# SENSORS.net
KiCad netlist of a schematic drawn in Altium Designer
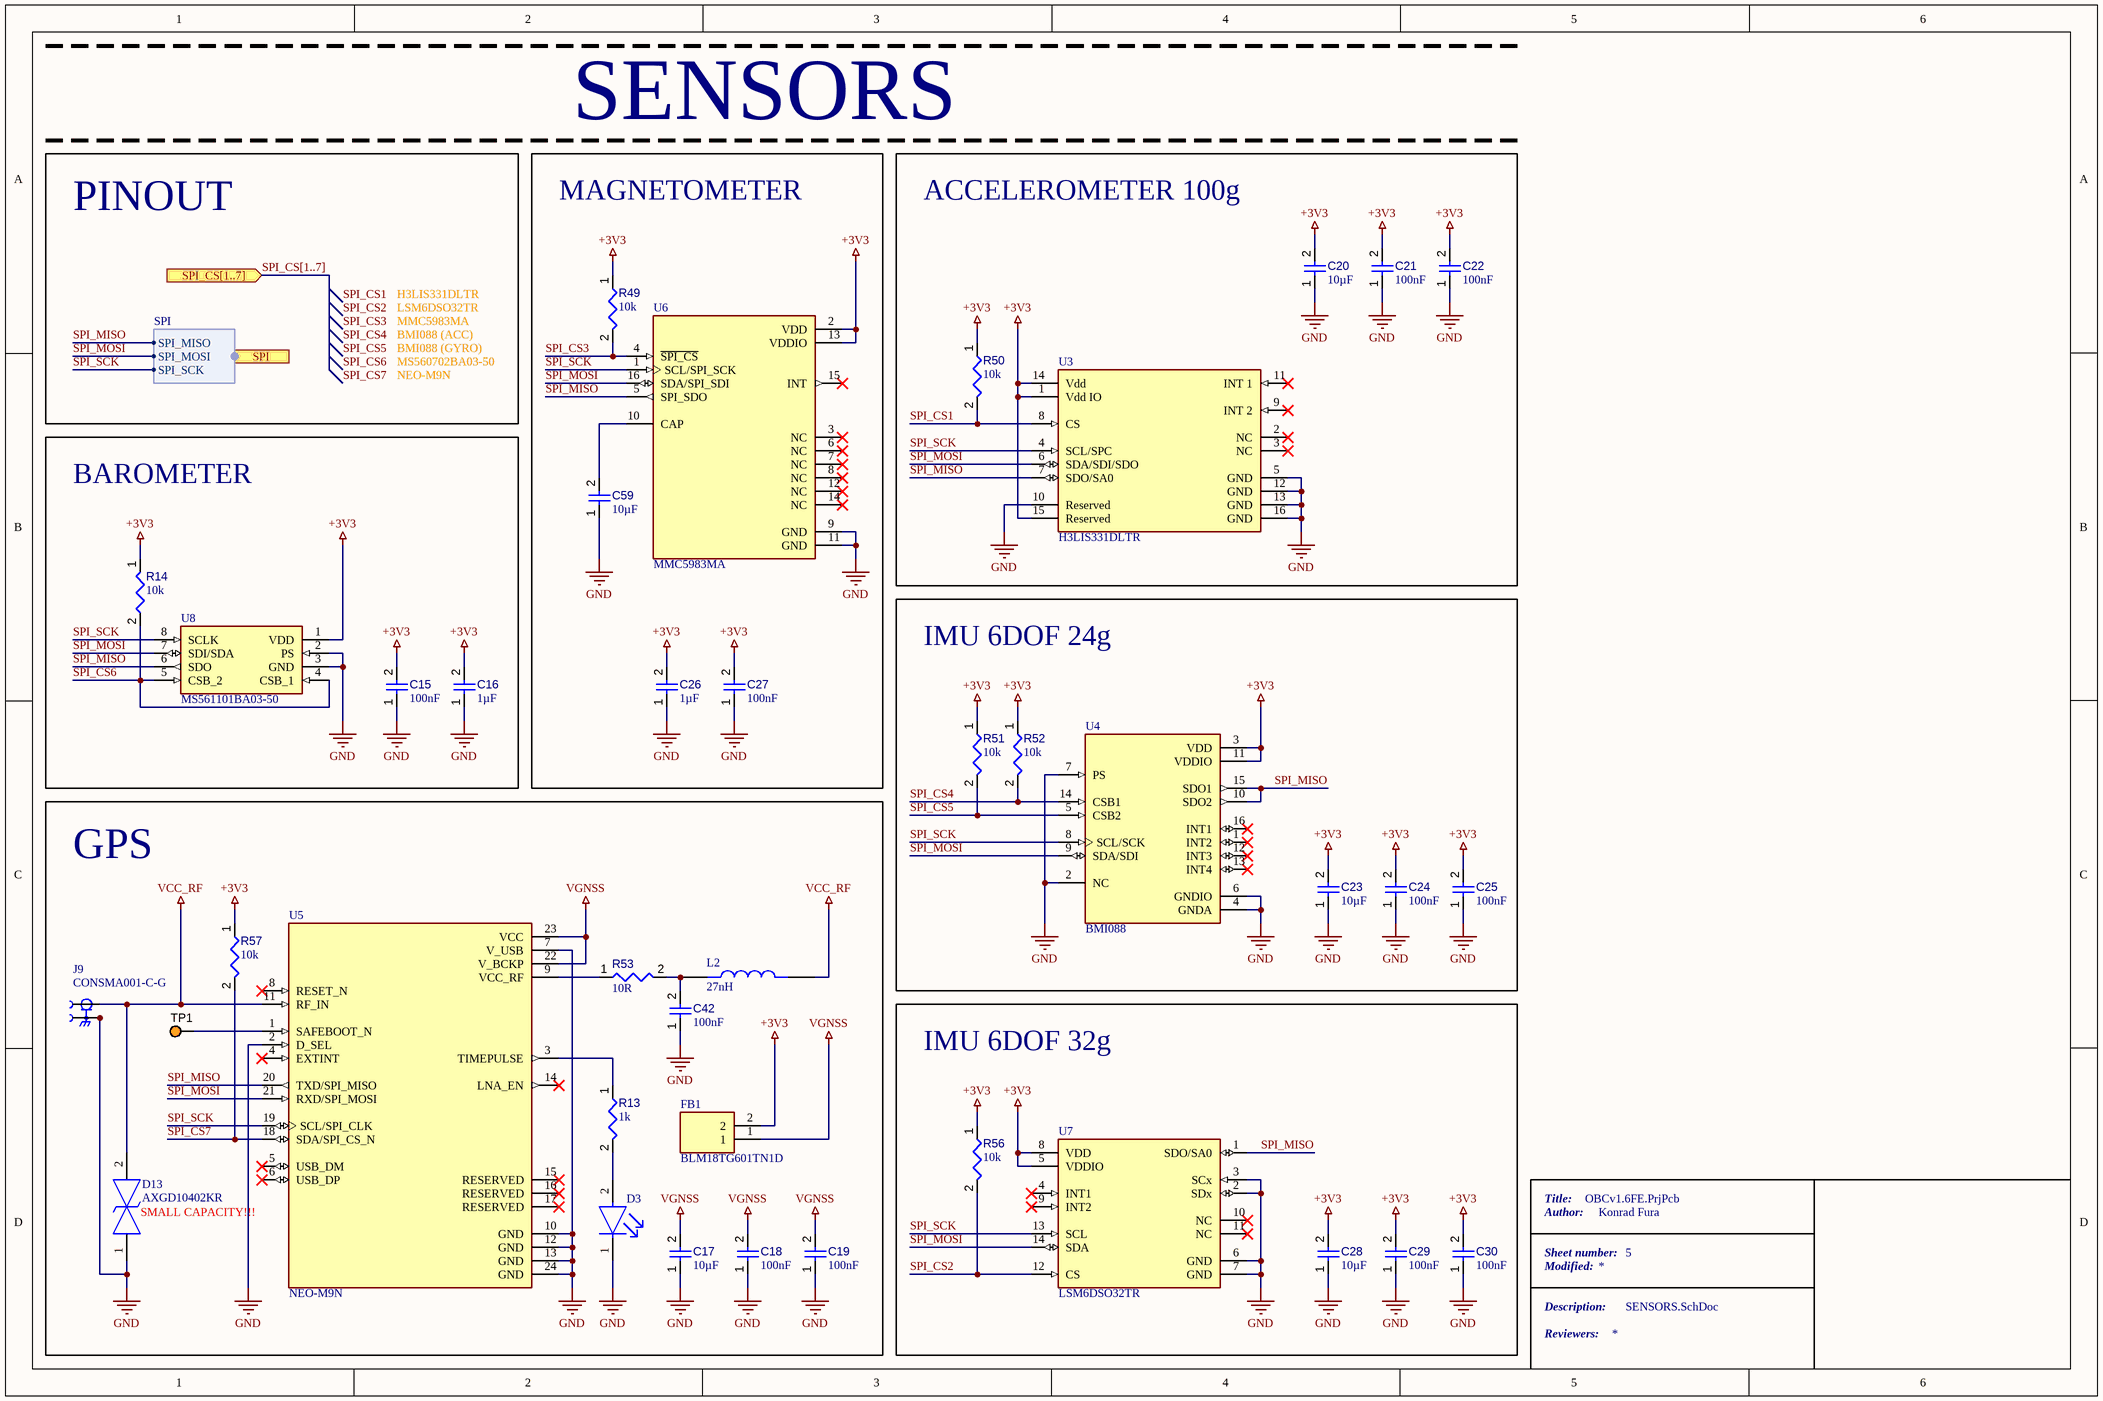
[diagram p0: SENSORS.SchDoc]

(export (version "E")
  (design (tool "Eeschema 10.0.6"))
  (components
    (comp (ref "C15")
      (value "100nF")
      (footprint "CAPC0402(1005)60_L")
      (description "Chip Capacitor, 100nF +/-20%, 10V, 0402, Thickness 0.6 mm")
      (fields (field (name "TOLERANCE") "20%") (field (name "Comment") "Capacitor 100nF +/-20% 10V 0402"))
      (libsource (lib "PWr in Space team") (part "CAP-NP-2"))
    )
    (comp (ref "C16")
      (value "1µF")
      (footprint "CAPC0402(1005)60_L")
      (description "Chip Capacitor, 1µF +/-20%, 10V, 0402, Thickness 0.6 mm")
      (fields (field (name "TOLERANCE") "10%") (field (name "Comment") "Capacitor 1µF +/-20% 10V 0402"))
      (libsource (lib "PWr in Space team") (part "CAP-NP-2"))
    )
    (comp (ref "C17")
      (value "10µF")
      (footprint "CAPC0603(1608)100_L")
      (description "Chip Capacitor, 10µF +/-20%, 10V, 0603, Thickness 1 mm")
      (fields (field (name "TOLERANCE") "10%") (field (name "Comment") "Capacitor 10µF +/-20% 10V 0603"))
      (libsource (lib "PWr in Space team") (part "CAP-NP-2"))
    )
    (comp (ref "C18")
      (value "100nF")
      (footprint "CAPC0402(1005)60_L")
      (description "Chip Capacitor, 100nF +/-20%, 10V, 0402, Thickness 0.6 mm")
      (fields (field (name "TOLERANCE") "20%") (field (name "Comment") "Capacitor 100nF +/-20% 10V 0402"))
      (libsource (lib "PWr in Space team") (part "CAP-NP-2"))
    )
    (comp (ref "C19")
      (value "100nF")
      (footprint "CAPC0402(1005)60_L")
      (description "Chip Capacitor, 100nF +/-20%, 10V, 0402, Thickness 0.6 mm")
      (fields (field (name "TOLERANCE") "20%") (field (name "Comment") "Capacitor 100nF +/-20% 10V 0402"))
      (libsource (lib "PWr in Space team") (part "CAP-NP-2"))
    )
    (comp (ref "C20")
      (value "10µF")
      (footprint "CAPC0603(1608)100_L")
      (description "Chip Capacitor, 10µF +/-20%, 10V, 0603, Thickness 1 mm")
      (fields (field (name "TOLERANCE") "10%") (field (name "Comment") "Capacitor 10µF +/-20% 10V 0603"))
      (libsource (lib "PWr in Space team") (part "CAP-NP-2"))
    )
    (comp (ref "C21")
      (value "100nF")
      (footprint "CAPC0402(1005)60_L")
      (description "Chip Capacitor, 100nF +/-20%, 10V, 0402, Thickness 0.6 mm")
      (fields (field (name "TOLERANCE") "20%") (field (name "Comment") "Capacitor 100nF +/-20% 10V 0402"))
      (libsource (lib "PWr in Space team") (part "CAP-NP-2"))
    )
    (comp (ref "C22")
      (value "100nF")
      (footprint "CAPC0402(1005)60_L")
      (description "Chip Capacitor, 100nF +/-20%, 10V, 0402, Thickness 0.6 mm")
      (fields (field (name "TOLERANCE") "20%") (field (name "Comment") "Capacitor 100nF +/-20% 10V 0402"))
      (libsource (lib "PWr in Space team") (part "CAP-NP-2"))
    )
    (comp (ref "C23")
      (value "10µF")
      (footprint "CAPC0603(1608)100_L")
      (description "Chip Capacitor, 10µF +/-20%, 10V, 0603, Thickness 1 mm")
      (fields (field (name "TOLERANCE") "10%") (field (name "Comment") "Capacitor 10µF +/-20% 10V 0603"))
      (libsource (lib "PWr in Space team") (part "CAP-NP-2"))
    )
    (comp (ref "C24")
      (value "100nF")
      (footprint "CAPC0402(1005)60_L")
      (description "Chip Capacitor, 100nF +/-20%, 10V, 0402, Thickness 0.6 mm")
      (fields (field (name "TOLERANCE") "20%") (field (name "Comment") "Capacitor 100nF +/-20% 10V 0402"))
      (libsource (lib "PWr in Space team") (part "CAP-NP-2"))
    )
    (comp (ref "C25")
      (value "100nF")
      (footprint "CAPC0402(1005)60_L")
      (description "Chip Capacitor, 100nF +/-20%, 10V, 0402, Thickness 0.6 mm")
      (fields (field (name "TOLERANCE") "20%") (field (name "Comment") "Capacitor 100nF +/-20% 10V 0402"))
      (libsource (lib "PWr in Space team") (part "CAP-NP-2"))
    )
    (comp (ref "C26")
      (value "1µF")
      (footprint "CAPC0402(1005)60_L")
      (description "Chip Capacitor, 1µF +/-20%, 10V, 0402, Thickness 0.6 mm")
      (fields (field (name "TOLERANCE") "10%") (field (name "Comment") "Capacitor 1µF +/-20% 10V 0402"))
      (libsource (lib "PWr in Space team") (part "CAP-NP-2"))
    )
    (comp (ref "C27")
      (value "100nF")
      (footprint "CAPC0402(1005)60_L")
      (description "Chip Capacitor, 100nF +/-20%, 10V, 0402, Thickness 0.6 mm")
      (fields (field (name "TOLERANCE") "20%") (field (name "Comment") "Capacitor 100nF +/-20% 10V 0402"))
      (libsource (lib "PWr in Space team") (part "CAP-NP-2"))
    )
    (comp (ref "C28")
      (value "10µF")
      (footprint "CAPC0603(1608)100_L")
      (description "Chip Capacitor, 10µF +/-20%, 10V, 0603, Thickness 1 mm")
      (fields (field (name "TOLERANCE") "10%") (field (name "Comment") "Capacitor 10µF +/-20% 10V 0603"))
      (libsource (lib "PWr in Space team") (part "CAP-NP-2"))
    )
    (comp (ref "C29")
      (value "100nF")
      (footprint "CAPC0402(1005)60_L")
      (description "Chip Capacitor, 100nF +/-20%, 10V, 0402, Thickness 0.6 mm")
      (fields (field (name "TOLERANCE") "20%") (field (name "Comment") "Capacitor 100nF +/-20% 10V 0402"))
      (libsource (lib "PWr in Space team") (part "CAP-NP-2"))
    )
    (comp (ref "C30")
      (value "100nF")
      (footprint "CAPC0402(1005)60_L")
      (description "Chip Capacitor, 100nF +/-20%, 10V, 0402, Thickness 0.6 mm")
      (fields (field (name "TOLERANCE") "20%") (field (name "Comment") "Capacitor 100nF +/-20% 10V 0402"))
      (libsource (lib "PWr in Space team") (part "CAP-NP-2"))
    )
    (comp (ref "C42")
      (value "100nF")
      (footprint "CAPC0402(1005)60_L")
      (description "Chip Capacitor, 100nF +/-20%, 10V, 0402, Thickness 0.6 mm")
      (fields (field (name "TOLERANCE") "20%") (field (name "Comment") "Capacitor 100nF +/-20% 10V 0402"))
      (libsource (lib "PWr in Space team") (part "CAP-NP-2"))
    )
    (comp (ref "C59")
      (value "10µF")
      (footprint "CAPC0603(1608)100_L")
      (description "Chip Capacitor, 10µF +/-20%, 10V, 0603, Thickness 1 mm")
      (fields (field (name "TOLERANCE") "10%") (field (name "Comment") "Capacitor 10µF +/-20% 10V 0603"))
      (libsource (lib "PWr in Space team") (part "CAP-NP-2"))
    )
    (comp (ref "D3")
      (value "D3")
      (footprint "FP-LTST-C191TBKT-MFG")
      (description "LED BLUE CLEAR CHIP SMD")
      (libsource (lib "Altium Content Vault") (part "8706943c75ba83719d021d2fdc84c58"))
    )
    (comp (ref "D13")
      (value "AXGD10402KR")
      (footprint "SamacSys:DIONM105X51N")
      (description "TVS Diode (Bi-directional)")
      (fields (field (name "MOUSER PART NUMBER") "576-AXGD10402KR"))
      (libsource (lib "*") (part "AXGD10402KR"))
    )
    (comp (ref "FB1")
      (value "BLM18TG601TN1D")
      (footprint "SamacSys:BLM18EG101TH1D")
      (description "Ferrite Bead")
      (fields (field (name "MOUSER PART NUMBER") "81-BLM18TG601TN1D"))
      (libsource (lib "*") (part "BLM18TG601TN1D"))
    )
    (comp (ref "J9")
      (value "CONSMA001-C-G")
      (footprint "LINX_CONSMA001-C-G")
      (fields (field (name "MF") "{'manufacturer': u'Linx Technologies'}"))
      (libsource (lib "SnapEDA_Library") (part "CONSMA001-C-G"))
    )
    (comp (ref "L2")
      (value "27nH")
      (footprint "INDC1005X65N")
      (description "IND 27nH 0.3A 1000mâ„¦")
      (fields (field (name "MF") "{'manufacturer': u'Abracon'}") (field (name "MP") "AIMC-0402-27NJ-T"))
      (libsource (lib "SnapEDA_Library") (part "AIMC-0402-27NJ-T"))
    )
    (comp (ref "R13")
      (value "1k")
      (footprint "RESC0402(1005)_L")
      (description "Chip Resistor, 1 kOhms, +/-5 %, 63 mW, -55 to 155 degC, 0402")
      (fields (field (name "TOLERANCE") "5%") (field (name "POWER") "63mW"))
      (libsource (lib "PWr in Space team") (part "RES-2"))
    )
    (comp (ref "R14")
      (value "10k")
      (footprint "RESC0402(1005)_L")
      (description "Chip Resistor, 10 kOhms, +/-1 %, 63 mW, -55 to 125 degC, 0402")
      (fields (field (name "POWER") "63mW") (field (name "TOLERANCE") "1%"))
      (libsource (lib "PWr in Space team") (part "RES-2"))
    )
    (comp (ref "R49")
      (value "10k")
      (footprint "RESC0402(1005)_L")
      (description "Chip Resistor, 10 kOhms, +/-1 %, 63 mW, -55 to 125 degC, 0402")
      (fields (field (name "POWER") "63mW") (field (name "TOLERANCE") "1%"))
      (libsource (lib "PWr in Space team") (part "RES-2"))
    )
    (comp (ref "R50")
      (value "10k")
      (footprint "RESC0402(1005)_L")
      (description "Chip Resistor, 10 kOhms, +/-1 %, 63 mW, -55 to 125 degC, 0402")
      (fields (field (name "POWER") "63mW") (field (name "TOLERANCE") "1%"))
      (libsource (lib "PWr in Space team") (part "RES-2"))
    )
    (comp (ref "R51")
      (value "10k")
      (footprint "RESC0402(1005)_L")
      (description "Chip Resistor, 10 kOhms, +/-1 %, 63 mW, -55 to 125 degC, 0402")
      (fields (field (name "POWER") "63mW") (field (name "TOLERANCE") "1%"))
      (libsource (lib "PWr in Space team") (part "RES-2"))
    )
    (comp (ref "R52")
      (value "10k")
      (footprint "RESC0402(1005)_L")
      (description "Chip Resistor, 10 kOhms, +/-1 %, 63 mW, -55 to 125 degC, 0402")
      (fields (field (name "POWER") "63mW") (field (name "TOLERANCE") "1%"))
      (libsource (lib "PWr in Space team") (part "RES-2"))
    )
    (comp (ref "R53")
      (value "10R")
      (footprint "RESC0402(1005)_L")
      (description "Chip Resistor, 10 Ohms, +/-1 %, 63 mW, -55 to 155 degC, 0402")
      (fields (field (name "TOLERANCE") "1%") (field (name "POWER") "63mW"))
      (libsource (lib "PWr in Space team") (part "RES-2"))
    )
    (comp (ref "R56")
      (value "10k")
      (footprint "RESC0402(1005)_L")
      (description "Chip Resistor, 10 kOhms, +/-1 %, 63 mW, -55 to 125 degC, 0402")
      (fields (field (name "POWER") "63mW") (field (name "TOLERANCE") "1%"))
      (libsource (lib "PWr in Space team") (part "RES-2"))
    )
    (comp (ref "R57")
      (value "10k")
      (footprint "RESC0402(1005)_L")
      (description "Chip Resistor, 10 kOhms, +/-1 %, 63 mW, -55 to 125 degC, 0402")
      (fields (field (name "POWER") "63mW") (field (name "TOLERANCE") "1%"))
      (libsource (lib "PWr in Space team") (part "RES-2"))
    )
    (comp (ref "TP1")
      (value "5003")
      (footprint "KSTN-5003")
      (description "Test Point, Orange, Height 4.6 mm, Tail Length 3 mm, 1-Pin THD, RoHS")
      (fields (field (name "MANUFACTURER") "Keystone"))
      (libsource (lib "PWr in Space team") (part "TESTPOINT_ORANGE"))
    )
    (comp (ref "U3")
      (value "H3LIS331DLTR")
      (footprint "FP-TFLGA16-7983231-MFG")
      (description "ACCEL 100-400G I2C/SPI 16TFLGA")
      (fields
        (field (name "OCTOPART") "https://octopart.com/h3lis331dltr-stmicroelectronics-29186499")
        (field (name "MANUFACTURER") "STMicroelectronics")
      )
      (libsource (lib "Altium Content Vault") (part "88bf36ed36dec8c6247366cd2bff627"))
    )
    (comp (ref "U4")
      (value "BMI088")
      (footprint "PQFN50P450X300X100-16N")
      (fields (field (name "MF") "{'manufacturer': u'Bosch Sensortec'}"))
      (libsource (lib "SnapEDA_Library") (part "BMI088"))
    )
    (comp (ref "U5")
      (value "NEO-M9N")
      (footprint "XCVR_NEO-M9N")
      (fields (field (name "MF") "{'manufacturer': u'U-Blox'}"))
      (libsource (lib "SnapEDA_Library") (part "NEO-M9N"))
    )
    (comp (ref "U6")
      (value "MMC5983MA")
      (footprint "PQFN50P300X300X100-16N")
      (description "MMC5983 series Magnetic, Magnetometer Sensor Evaluation Board")
      (fields (field (name "MF") "{'manufacturer': u'Memsic Inc.'}"))
      (libsource (lib "SnapEDA_Library") (part "MMC5983MA"))
    )
    (comp (ref "U7")
      (value "LSM6DSO32TR")
      (footprint "FP-LGA-14L-DM00249496-MFG")
      (description "INEMO INERTIAL MODULE: 3D ACCELE")
      (libsource (lib "Altium Content Vault") (part "593856c316c551aebc7657d93cdb4f0"))
    )
    (comp (ref "U8")
      (value "MS561101BA03-50")
      (footprint "SamacSys:MS561101BA03-50")
      (description "Integrated Circuit")
      (fields (field (name "MOUSER PART NUMBER") "824-MS561101BA03-50"))
      (libsource (lib "*") (part "MS561101BA03-50"))
    )
  )
  (nets
    (net (code "2") (name "+3V3") (class "Default")
      (node (ref "C15") (pin "2") (pinfunction "2_2") (pintype "passive"))
      (node (ref "C16") (pin "2") (pinfunction "2_2") (pintype "passive"))
      (node (ref "C20") (pin "2") (pinfunction "2_2") (pintype "passive"))
      (node (ref "C21") (pin "2") (pinfunction "2_2") (pintype "passive"))
      (node (ref "C22") (pin "2") (pinfunction "2_2") (pintype "passive"))
      (node (ref "C23") (pin "2") (pinfunction "2_2") (pintype "passive"))
      (node (ref "C24") (pin "2") (pinfunction "2_2") (pintype "passive"))
      (node (ref "C25") (pin "2") (pinfunction "2_2") (pintype "passive"))
      (node (ref "C26") (pin "2") (pinfunction "2_2") (pintype "passive"))
      (node (ref "C27") (pin "2") (pinfunction "2_2") (pintype "passive"))
      (node (ref "C28") (pin "2") (pinfunction "2_2") (pintype "passive"))
      (node (ref "C29") (pin "2") (pinfunction "2_2") (pintype "passive"))
      (node (ref "C30") (pin "2") (pinfunction "2_2") (pintype "passive"))
      (node (ref "FB1") (pin "2") (pinfunction "2_2") (pintype "passive"))
      (node (ref "R14") (pin "1") (pinfunction "1_1") (pintype "passive"))
      (node (ref "R49") (pin "1") (pinfunction "1_1") (pintype "passive"))
      (node (ref "R50") (pin "1") (pinfunction "1_1") (pintype "passive"))
      (node (ref "R51") (pin "1") (pinfunction "1_1") (pintype "passive"))
      (node (ref "R52") (pin "1") (pinfunction "1_1") (pintype "passive"))
      (node (ref "R56") (pin "1") (pinfunction "1_1") (pintype "passive"))
      (node (ref "R57") (pin "1") (pinfunction "1_1") (pintype "passive"))
      (node (ref "U3") (pin "1") (pinfunction "Vdd_IO_1") (pintype "power_in"))
      (node (ref "U3") (pin "14") (pinfunction "Vdd_14") (pintype "power_in"))
      (node (ref "U3") (pin "15") (pinfunction "Reserved_15") (pintype "passive"))
      (node (ref "U4") (pin "11") (pinfunction "VDDIO_11") (pintype "power_in"))
      (node (ref "U4") (pin "3") (pinfunction "VDD_3") (pintype "power_in"))
      (node (ref "U6") (pin "13") (pinfunction "VDDIO_13") (pintype "power_in"))
      (node (ref "U6") (pin "2") (pinfunction "VDD_2") (pintype "power_in"))
      (node (ref "U7") (pin "5") (pinfunction "VDDIO_5") (pintype "power_in"))
      (node (ref "U7") (pin "8") (pinfunction "VDD_8") (pintype "power_in"))
      (node (ref "U8") (pin "1") (pinfunction "VDD_1") (pintype "power_in"))
    )
    (net (code "3") (name "/SPI_CS1") (class "Default")
      (node (ref "R50") (pin "2") (pinfunction "2_2") (pintype "passive"))
      (node (ref "U3") (pin "8") (pinfunction "CS_8") (pintype "input"))
    )
    (net (code "4") (name "/SPI_CS2") (class "Default")
      (node (ref "R56") (pin "2") (pinfunction "2_2") (pintype "passive"))
      (node (ref "U7") (pin "12") (pinfunction "CS_12") (pintype "input"))
    )
    (net (code "5") (name "/SPI_CS3") (class "Default")
      (node (ref "R49") (pin "2") (pinfunction "2_2") (pintype "passive"))
      (node (ref "U6") (pin "4") (pinfunction "~{SPI_CS}_4") (pintype "input"))
    )
    (net (code "6") (name "/SPI_CS4") (class "Default")
      (node (ref "R52") (pin "2") (pinfunction "2_2") (pintype "passive"))
      (node (ref "U4") (pin "14") (pinfunction "CSB1_14") (pintype "input"))
    )
    (net (code "7") (name "/SPI_CS5") (class "Default")
      (node (ref "R51") (pin "2") (pinfunction "2_2") (pintype "passive"))
      (node (ref "U4") (pin "5") (pinfunction "CSB2_5") (pintype "input"))
    )
    (net (code "8") (name "/SPI_CS6") (class "Default")
      (node (ref "R14") (pin "2") (pinfunction "2_2") (pintype "passive"))
      (node (ref "U8") (pin "4") (pinfunction "CSB_1_4") (pintype "input"))
      (node (ref "U8") (pin "5") (pinfunction "CSB_2_5") (pintype "input"))
    )
    (net (code "9") (name "/SPI_CS7") (class "Default")
      (node (ref "R57") (pin "2") (pinfunction "2_2") (pintype "passive"))
      (node (ref "U5") (pin "18") (pinfunction "SDA/SPI_CS_N_18") (pintype "bidirectional"))
    )
    (net (code "11") (name "/SPI_MISO") (class "Default")
      (node (ref "U3") (pin "7") (pinfunction "SDO/SA0_7") (pintype "bidirectional"))
      (node (ref "U4") (pin "10") (pinfunction "SDO2_10") (pintype "output"))
      (node (ref "U4") (pin "15") (pinfunction "SDO1_15") (pintype "output"))
      (node (ref "U5") (pin "20") (pinfunction "TXD/SPI_MISO_20") (pintype "output"))
      (node (ref "U6") (pin "5") (pinfunction "SPI_SDO_5") (pintype "output"))
      (node (ref "U7") (pin "1") (pinfunction "SDO/SA0_1") (pintype "bidirectional"))
      (node (ref "U8") (pin "6") (pinfunction "SDO_6") (pintype "output"))
    )
    (net (code "12") (name "/SPI_MOSI") (class "Default")
      (node (ref "U3") (pin "6") (pinfunction "SDA/SDI/SDO_6") (pintype "bidirectional"))
      (node (ref "U4") (pin "9") (pinfunction "SDA/SDI_9") (pintype "bidirectional"))
      (node (ref "U5") (pin "21") (pinfunction "RXD/SPI_MOSI_21") (pintype "input"))
      (node (ref "U6") (pin "16") (pinfunction "SDA/SPI_SDI_16") (pintype "bidirectional"))
      (node (ref "U7") (pin "14") (pinfunction "SDA_14") (pintype "bidirectional"))
      (node (ref "U8") (pin "7") (pinfunction "SDI/SDA_7") (pintype "bidirectional"))
    )
    (net (code "13") (name "/SPI_SCK") (class "Default")
      (node (ref "U3") (pin "4") (pinfunction "SCL/SPC_4") (pintype "input"))
      (node (ref "U4") (pin "8") (pinfunction "SCL/SCK_8") (pintype "input"))
      (node (ref "U5") (pin "19") (pinfunction "SCL/SPI_CLK_19") (pintype "bidirectional"))
      (node (ref "U6") (pin "1") (pinfunction "SCL/SPI_SCK_1") (pintype "input"))
      (node (ref "U7") (pin "13") (pinfunction "SCL_13") (pintype "input"))
      (node (ref "U8") (pin "8") (pinfunction "SCLK_8") (pintype "input"))
    )
    (net (code "15") (name "GND") (class "Default")
      (node (ref "C15") (pin "1") (pinfunction "1_1") (pintype "passive"))
      (node (ref "C16") (pin "1") (pinfunction "1_1") (pintype "passive"))
      (node (ref "C17") (pin "1") (pinfunction "1_1") (pintype "passive"))
      (node (ref "C18") (pin "1") (pinfunction "1_1") (pintype "passive"))
      (node (ref "C19") (pin "1") (pinfunction "1_1") (pintype "passive"))
      (node (ref "C20") (pin "1") (pinfunction "1_1") (pintype "passive"))
      (node (ref "C21") (pin "1") (pinfunction "1_1") (pintype "passive"))
      (node (ref "C22") (pin "1") (pinfunction "1_1") (pintype "passive"))
      (node (ref "C23") (pin "1") (pinfunction "1_1") (pintype "passive"))
      (node (ref "C24") (pin "1") (pinfunction "1_1") (pintype "passive"))
      (node (ref "C25") (pin "1") (pinfunction "1_1") (pintype "passive"))
      (node (ref "C26") (pin "1") (pinfunction "1_1") (pintype "passive"))
      (node (ref "C27") (pin "1") (pinfunction "1_1") (pintype "passive"))
      (node (ref "C28") (pin "1") (pinfunction "1_1") (pintype "passive"))
      (node (ref "C29") (pin "1") (pinfunction "1_1") (pintype "passive"))
      (node (ref "C30") (pin "1") (pinfunction "1_1") (pintype "passive"))
      (node (ref "C42") (pin "1") (pinfunction "1_1") (pintype "passive"))
      (node (ref "C59") (pin "1") (pinfunction "1_1") (pintype "passive"))
      (node (ref "D13") (pin "1") (pinfunction "1_1") (pintype "passive"))
      (node (ref "D3") (pin "1") (pinfunction "C_1") (pintype "passive"))
      (node (ref "J9") (pin "S1") (pinfunction "2_S1") (pintype "passive"))
      (node (ref "J9") (pin "S2") (pinfunction "2_S2") (pintype "passive"))
      (node (ref "J9") (pin "S3") (pinfunction "2_S3") (pintype "passive"))
      (node (ref "J9") (pin "S4") (pinfunction "2_S4") (pintype "passive"))
      (node (ref "U3") (pin "10") (pinfunction "Reserved_10") (pintype "passive"))
      (node (ref "U3") (pin "12") (pinfunction "GND_12") (pintype "power_in"))
      (node (ref "U3") (pin "13") (pinfunction "GND_13") (pintype "power_in"))
      (node (ref "U3") (pin "16") (pinfunction "GND_16") (pintype "power_in"))
      (node (ref "U3") (pin "5") (pinfunction "GND_5") (pintype "power_in"))
      (node (ref "U4") (pin "2") (pinfunction "NC_2") (pintype "passive"))
      (node (ref "U4") (pin "4") (pinfunction "GNDA_4") (pintype "power_in"))
      (node (ref "U4") (pin "6") (pinfunction "GNDIO_6") (pintype "power_in"))
      (node (ref "U4") (pin "7") (pinfunction "PS_7") (pintype "input"))
      (node (ref "U5") (pin "10") (pinfunction "GND_10") (pintype "power_in"))
      (node (ref "U5") (pin "12") (pinfunction "GND_12") (pintype "power_in"))
      (node (ref "U5") (pin "13") (pinfunction "GND_13") (pintype "power_in"))
      (node (ref "U5") (pin "2") (pinfunction "D_SEL_2") (pintype "input"))
      (node (ref "U5") (pin "24") (pinfunction "GND_24") (pintype "power_in"))
      (node (ref "U5") (pin "7") (pinfunction "V_USB_7") (pintype "power_in"))
      (node (ref "U6") (pin "11") (pinfunction "GND_11") (pintype "power_in"))
      (node (ref "U6") (pin "9") (pinfunction "GND_9") (pintype "power_in"))
      (node (ref "U7") (pin "2") (pinfunction "SDx_2") (pintype "bidirectional"))
      (node (ref "U7") (pin "3") (pinfunction "SCx_3") (pintype "input"))
      (node (ref "U7") (pin "6") (pinfunction "GND_6") (pintype "power_in"))
      (node (ref "U7") (pin "7") (pinfunction "GND_7") (pintype "power_in"))
      (node (ref "U8") (pin "2") (pinfunction "PS_2") (pintype "input"))
      (node (ref "U8") (pin "3") (pinfunction "GND_3") (pintype "power_in"))
    )
    (net (code "16") (name "Net-(C42-Pad2)") (class "Default")
      (node (ref "C42") (pin "2") (pinfunction "2_2") (pintype "passive"))
      (node (ref "L2") (pin "1") (pinfunction "1_1") (pintype "passive"))
      (node (ref "R53") (pin "2") (pinfunction "2_2") (pintype "passive"))
    )
    (net (code "17") (name "Net-(D3-A)") (class "Default")
      (node (ref "D3") (pin "2") (pinfunction "A_2") (pintype "passive"))
      (node (ref "R13") (pin "2") (pinfunction "2_2") (pintype "passive"))
    )
    (net (code "18") (name "Net-(U5-SAFEBOOT_N)") (class "Default")
      (node (ref "TP1") (pin "1") (pinfunction "1_1") (pintype "passive"))
      (node (ref "U5") (pin "1") (pinfunction "SAFEBOOT_N_1") (pintype "input"))
    )
    (net (code "19") (name "Net-(U5-TIMEPULSE)") (class "Default")
      (node (ref "R13") (pin "1") (pinfunction "1_1") (pintype "passive"))
      (node (ref "U5") (pin "3") (pinfunction "TIMEPULSE_3") (pintype "output"))
    )
    (net (code "20") (name "Net-(U5-VCC_RF)") (class "Default")
      (node (ref "R53") (pin "1") (pinfunction "1_1") (pintype "passive"))
      (node (ref "U5") (pin "9") (pinfunction "VCC_RF_9") (pintype "power_in"))
    )
    (net (code "21") (name "Net-(U6-CAP)") (class "Default")
      (node (ref "C59") (pin "2") (pinfunction "2_2") (pintype "passive"))
      (node (ref "U6") (pin "10") (pinfunction "CAP_10") (pintype "passive"))
    )
    (net (code "22") (name "VCC_RF") (class "Default")
      (node (ref "D13") (pin "2") (pinfunction "2_2") (pintype "passive"))
      (node (ref "J9") (pin "1") (pinfunction "1_1") (pintype "passive"))
      (node (ref "L2") (pin "2") (pinfunction "2_2") (pintype "passive"))
      (node (ref "U5") (pin "11") (pinfunction "RF_IN_11") (pintype "input"))
    )
    (net (code "23") (name "VGNSS") (class "Default")
      (node (ref "C17") (pin "2") (pinfunction "2_2") (pintype "passive"))
      (node (ref "C18") (pin "2") (pinfunction "2_2") (pintype "passive"))
      (node (ref "C19") (pin "2") (pinfunction "2_2") (pintype "passive"))
      (node (ref "FB1") (pin "1") (pinfunction "1_1") (pintype "passive"))
      (node (ref "U5") (pin "22") (pinfunction "V_BCKP_22") (pintype "power_in"))
      (node (ref "U5") (pin "23") (pinfunction "VCC_23") (pintype "power_in"))
    )
    (net (code "24") (name "unconnected-(U3-INT_1-Pad11)") (class "Default")
      (node (ref "U3") (pin "11") (pinfunction "INT_1_11") (pintype "input+no_connect"))
    )
    (net (code "25") (name "unconnected-(U3-INT_2-Pad9)") (class "Default")
      (node (ref "U3") (pin "9") (pinfunction "INT_2_9") (pintype "input+no_connect"))
    )
    (net (code "26") (name "unconnected-(U3-NC-Pad2)") (class "Default")
      (node (ref "U3") (pin "2") (pinfunction "NC_2") (pintype "passive+no_connect"))
    )
    (net (code "27") (name "unconnected-(U3-NC-Pad3)") (class "Default")
      (node (ref "U3") (pin "3") (pinfunction "NC_3") (pintype "passive+no_connect"))
    )
    (net (code "28") (name "unconnected-(U4-INT1-Pad16)") (class "Default")
      (node (ref "U4") (pin "16") (pinfunction "INT1_16") (pintype "bidirectional+no_connect"))
    )
    (net (code "29") (name "unconnected-(U4-INT2-Pad1)") (class "Default")
      (node (ref "U4") (pin "1") (pinfunction "INT2_1") (pintype "bidirectional+no_connect"))
    )
    (net (code "30") (name "unconnected-(U4-INT3-Pad12)") (class "Default")
      (node (ref "U4") (pin "12") (pinfunction "INT3_12") (pintype "bidirectional+no_connect"))
    )
    (net (code "31") (name "unconnected-(U4-INT4-Pad13)") (class "Default")
      (node (ref "U4") (pin "13") (pinfunction "INT4_13") (pintype "bidirectional+no_connect"))
    )
    (net (code "32") (name "unconnected-(U5-EXTINT-Pad4)") (class "Default")
      (node (ref "U5") (pin "4") (pinfunction "EXTINT_4") (pintype "input+no_connect"))
    )
    (net (code "33") (name "unconnected-(U5-LNA_EN-Pad14)") (class "Default")
      (node (ref "U5") (pin "14") (pinfunction "LNA_EN_14") (pintype "output+no_connect"))
    )
    (net (code "34") (name "unconnected-(U5-RESERVED-Pad15)") (class "Default")
      (node (ref "U5") (pin "15") (pinfunction "RESERVED_15") (pintype "passive+no_connect"))
    )
    (net (code "35") (name "unconnected-(U5-RESERVED-Pad16)") (class "Default")
      (node (ref "U5") (pin "16") (pinfunction "RESERVED_16") (pintype "passive+no_connect"))
    )
    (net (code "36") (name "unconnected-(U5-RESERVED-Pad17)") (class "Default")
      (node (ref "U5") (pin "17") (pinfunction "RESERVED_17") (pintype "passive+no_connect"))
    )
    (net (code "37") (name "unconnected-(U5-RESET_N-Pad8)") (class "Default")
      (node (ref "U5") (pin "8") (pinfunction "RESET_N_8") (pintype "input+no_connect"))
    )
    (net (code "38") (name "unconnected-(U5-USB_DM-Pad5)") (class "Default")
      (node (ref "U5") (pin "5") (pinfunction "USB_DM_5") (pintype "bidirectional+no_connect"))
    )
    (net (code "39") (name "unconnected-(U5-USB_DP-Pad6)") (class "Default")
      (node (ref "U5") (pin "6") (pinfunction "USB_DP_6") (pintype "bidirectional+no_connect"))
    )
    (net (code "40") (name "unconnected-(U6-INT-Pad15)") (class "Default")
      (node (ref "U6") (pin "15") (pinfunction "INT_15") (pintype "output+no_connect"))
    )
    (net (code "41") (name "unconnected-(U6-NC-Pad3)") (class "Default")
      (node (ref "U6") (pin "3") (pinfunction "NC_3") (pintype "passive+no_connect"))
    )
    (net (code "42") (name "unconnected-(U6-NC-Pad6)") (class "Default")
      (node (ref "U6") (pin "6") (pinfunction "NC_6") (pintype "passive+no_connect"))
    )
    (net (code "43") (name "unconnected-(U6-NC-Pad7)") (class "Default")
      (node (ref "U6") (pin "7") (pinfunction "NC_7") (pintype "passive+no_connect"))
    )
    (net (code "44") (name "unconnected-(U6-NC-Pad8)") (class "Default")
      (node (ref "U6") (pin "8") (pinfunction "NC_8") (pintype "passive+no_connect"))
    )
    (net (code "45") (name "unconnected-(U6-NC-Pad12)") (class "Default")
      (node (ref "U6") (pin "12") (pinfunction "NC_12") (pintype "passive+no_connect"))
    )
    (net (code "46") (name "unconnected-(U6-NC-Pad14)") (class "Default")
      (node (ref "U6") (pin "14") (pinfunction "NC_14") (pintype "passive+no_connect"))
    )
    (net (code "47") (name "unconnected-(U7-INT1-Pad4)") (class "Default")
      (node (ref "U7") (pin "4") (pinfunction "INT1_4") (pintype "input+no_connect"))
    )
    (net (code "48") (name "unconnected-(U7-INT2-Pad9)") (class "Default")
      (node (ref "U7") (pin "9") (pinfunction "INT2_9") (pintype "input+no_connect"))
    )
    (net (code "49") (name "unconnected-(U7-NC-Pad10)") (class "Default")
      (node (ref "U7") (pin "10") (pinfunction "NC_10") (pintype "passive+no_connect"))
    )
    (net (code "50") (name "unconnected-(U7-NC-Pad11)") (class "Default")
      (node (ref "U7") (pin "11") (pinfunction "NC_11") (pintype "passive+no_connect"))
    )
  )
)
